# Mag_Ang.net
KiCad netlist of a schematic drawn in Altium Designer
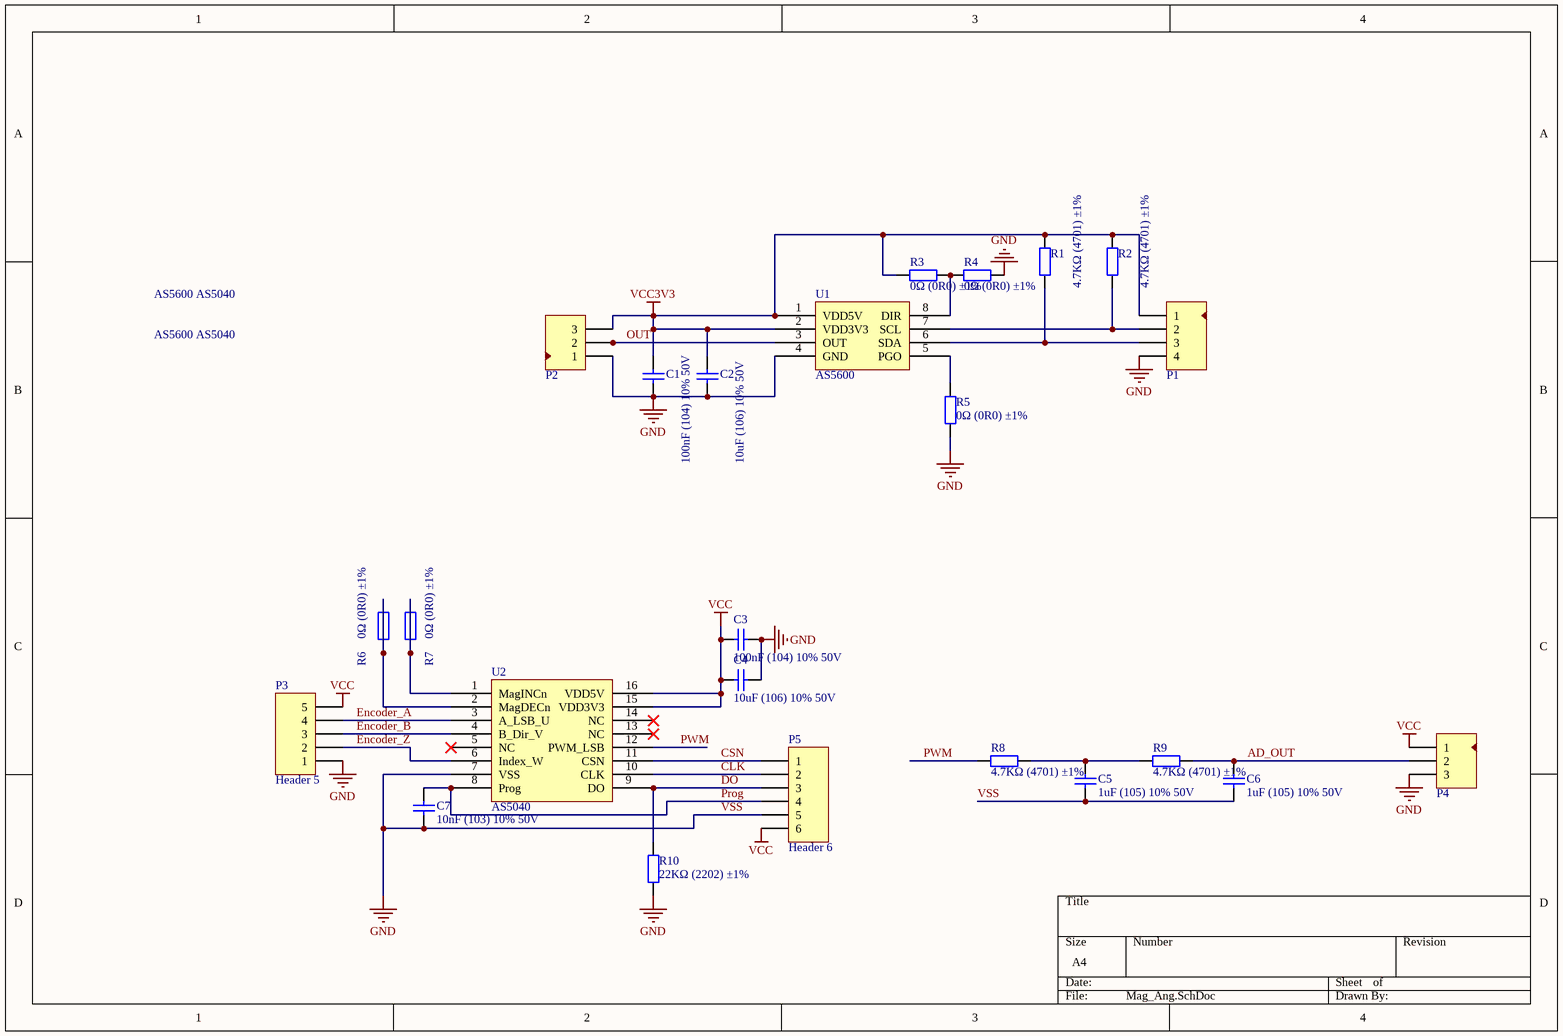
[diagram p0: Mag_Ang.SchDoc]

(export (version "E")
  (design (tool "Eeschema 10.0.6"))
  (components
    (comp (ref "C1")
      (value "100nF (104) 10% 50V")
      (footprint "0603_C")
      (description "贴片电容")
      (libsource (lib "Miscellaneous Devices LC") (part "0603 100nF (104) 10% 50V"))
    )
    (comp (ref "C2")
      (value "10uF (106) 10% 50V")
      (footprint "1206_C")
      (description "贴片电容")
      (libsource (lib "Miscellaneous Devices LC") (part "1206 10uF (106) 10% 50V"))
    )
    (comp (ref "C3")
      (value "100nF (104) 10% 50V")
      (footprint "0603_C")
      (description "贴片电容")
      (libsource (lib "Miscellaneous Devices LC") (part "0603 100nF (104) 10% 50V"))
    )
    (comp (ref "C4")
      (value "10uF (106) 10% 50V")
      (footprint "1206_C")
      (description "贴片电容")
      (libsource (lib "Miscellaneous Devices LC") (part "1206 10uF (106) 10% 50V"))
    )
    (comp (ref "C5")
      (value "1uF (105) 10% 50V")
      (footprint "0603_C")
      (description "贴片电容")
      (libsource (lib "Miscellaneous Devices LC") (part "0603 1uF (105) 10% 50V"))
    )
    (comp (ref "C6")
      (value "1uF (105) 10% 50V")
      (footprint "0603_C")
      (description "贴片电容")
      (libsource (lib "Miscellaneous Devices LC") (part "0603 1uF (105) 10% 50V"))
    )
    (comp (ref "C7")
      (value "10nF (103) 10% 50V")
      (footprint "0603_C")
      (description "贴片电容")
      (libsource (lib "Miscellaneous Devices LC") (part "0603 10nF (103) 10% 50V"))
    )
    (comp (ref "P1")
      (value "Header 4")
      (footprint "XH2.54-4P")
      (description "接插件")
      (fields (field (name "PUBLISHER") "Altium Limited"))
      (libsource (lib "HDR_fszhang") (part "Header 4"))
    )
    (comp (ref "P2")
      (value "Header 3")
      (footprint "KF2.54-3P")
      (description "接插件")
      (fields (field (name "PUBLISHER") "Altium Limited"))
      (libsource (lib "") (part "Header 3_1"))
    )
    (comp (ref "P3")
      (value "Header 5")
      (footprint "HDR1X5")
      (description "Header, 5-Pin")
      (fields (field (name "PUBLISHER") "Altium Limited"))
      (libsource (lib "Miscellaneous Connectors") (part "Header 5"))
    )
    (comp (ref "P4")
      (value "Header 3")
      (footprint "KF2.54-3P")
      (description "接插件")
      (fields (field (name "PUBLISHER") "Altium Limited"))
      (libsource (lib "HDR_fszhang") (part "Header 3"))
    )
    (comp (ref "P5")
      (value "Header 6")
      (footprint "HDR1X6")
      (description "Header, 6-Pin")
      (fields (field (name "PUBLISHER") "Altium Limited"))
      (libsource (lib "Miscellaneous Connectors") (part "Header 6"))
    )
    (comp (ref "R1")
      (value "4.7KΩ (4701) ±1%")
      (footprint "0603_R")
      (description "贴片电阻")
      (libsource (lib "") (part "0603 4.7KΩ (4701) 1%_1"))
    )
    (comp (ref "R2")
      (value "4.7KΩ (4701) ±1%")
      (footprint "0603_R")
      (description "贴片电阻")
      (libsource (lib "") (part "0603 4.7KΩ (4701) 1%_1"))
    )
    (comp (ref "R3")
      (value "0Ω (0R0) ±1%")
      (footprint "0603_R")
      (description "贴片电阻")
      (libsource (lib "") (part "0603 0Ω (0R0) 1%_1"))
    )
    (comp (ref "R4")
      (value "0Ω (0R0) ±1%")
      (footprint "0603_R")
      (description "贴片电阻")
      (libsource (lib "") (part "0603 0Ω (0R0) 1%_1"))
    )
    (comp (ref "R5")
      (value "0Ω (0R0) ±1%")
      (footprint "0603_R")
      (description "贴片电阻")
      (libsource (lib "") (part "0603 0Ω (0R0) 1%_2"))
    )
    (comp (ref "R6")
      (value "0Ω (0R0) ±1%")
      (footprint "0603_R")
      (description "贴片电阻")
      (libsource (lib "Miscellaneous Devices LC") (part "0603 0Ω (0R0) 1%"))
    )
    (comp (ref "R7")
      (value "0Ω (0R0) ±1%")
      (footprint "0603_R")
      (description "贴片电阻")
      (libsource (lib "Miscellaneous Devices LC") (part "0603 0Ω (0R0) 1%"))
    )
    (comp (ref "R8")
      (value "4.7KΩ (4701) ±1%")
      (footprint "0603_R")
      (description "贴片电阻")
      (libsource (lib "Miscellaneous Devices LC") (part "0603 4.7KΩ (4701) 1%"))
    )
    (comp (ref "R9")
      (value "4.7KΩ (4701) ±1%")
      (footprint "0603_R")
      (description "贴片电阻")
      (libsource (lib "Miscellaneous Devices LC") (part "0603 4.7KΩ (4701) 1%"))
    )
    (comp (ref "R10")
      (value "22KΩ (2202) ±1%")
      (footprint "0603_R")
      (description "贴片电阻")
      (libsource (lib "Miscellaneous Devices LC") (part "0603 22KΩ (2202) 1%"))
    )
    (comp (ref "U1") (value "AS5600") (footprint "RS2101S") (libsource (lib "Motorlib") (part "AS5600")))
    (comp (ref "U2")
      (value "AS5040")
      (footprint "SOP65P780X180-16N")
      (libsource (lib "Motorlib") (part "AS5040"))
    )
  )
  (nets
    (net (code "1") (name "/AD_OUT") (class "Default")
      (node (ref "C6") (pin "2") (pinfunction "2_2") (pintype "passive"))
      (node (ref "P4") (pin "2") (pinfunction "2_2") (pintype "passive"))
      (node (ref "R9") (pin "2") (pinfunction "2_2") (pintype "passive"))
    )
    (net (code "2") (name "/CLK") (class "Default")
      (node (ref "P5") (pin "2") (pinfunction "2_2") (pintype "passive"))
      (node (ref "U2") (pin "10") (pinfunction "CLK_10") (pintype "passive"))
    )
    (net (code "3") (name "/CSN") (class "Default")
      (node (ref "P5") (pin "1") (pinfunction "1_1") (pintype "passive"))
      (node (ref "U2") (pin "11") (pinfunction "CSN_11") (pintype "passive"))
    )
    (net (code "4") (name "/DO") (class "Default")
      (node (ref "P5") (pin "3") (pinfunction "3_3") (pintype "passive"))
      (node (ref "R10") (pin "2") (pinfunction "2_2") (pintype "passive"))
      (node (ref "U2") (pin "9") (pinfunction "DO_9") (pintype "passive"))
    )
    (net (code "5") (name "/Encoder_A") (class "Default")
      (node (ref "P3") (pin "4") (pinfunction "4_4") (pintype "passive"))
      (node (ref "U2") (pin "3") (pinfunction "A_LSB_U_3") (pintype "passive"))
    )
    (net (code "6") (name "/Encoder_B") (class "Default")
      (node (ref "P3") (pin "3") (pinfunction "3_3") (pintype "passive"))
      (node (ref "U2") (pin "4") (pinfunction "B_Dir_V_4") (pintype "passive"))
    )
    (net (code "7") (name "/Encoder_Z") (class "Default")
      (node (ref "P3") (pin "2") (pinfunction "2_2") (pintype "passive"))
      (node (ref "U2") (pin "6") (pinfunction "Index_W_6") (pintype "passive"))
    )
    (net (code "8") (name "/OUT") (class "Default")
      (node (ref "P2") (pin "2") (pinfunction "2_2") (pintype "passive"))
      (node (ref "U1") (pin "3") (pinfunction "OUT_3") (pintype "passive"))
    )
    (net (code "9") (name "/PWM") (class "Default")
      (node (ref "R8") (pin "1") (pinfunction "1_1") (pintype "passive"))
      (node (ref "U2") (pin "12") (pinfunction "PWM_LSB_12") (pintype "passive"))
    )
    (net (code "10") (name "/Prog") (class "Default")
      (node (ref "C7") (pin "2") (pinfunction "2_2") (pintype "passive"))
      (node (ref "P5") (pin "4") (pinfunction "4_4") (pintype "passive"))
      (node (ref "U2") (pin "8") (pinfunction "Prog_8") (pintype "passive"))
    )
    (net (code "11") (name "GND") (class "Default")
      (node (ref "C1") (pin "1") (pinfunction "1_1") (pintype "passive"))
      (node (ref "C2") (pin "1") (pinfunction "1_1") (pintype "passive"))
      (node (ref "C3") (pin "2") (pinfunction "2_2") (pintype "passive"))
      (node (ref "C4") (pin "1") (pinfunction "1_1") (pintype "passive"))
      (node (ref "C5") (pin "1") (pinfunction "1_1") (pintype "passive"))
      (node (ref "C6") (pin "1") (pinfunction "1_1") (pintype "passive"))
      (node (ref "C7") (pin "1") (pinfunction "1_1") (pintype "passive"))
      (node (ref "P1") (pin "4") (pinfunction "4_4") (pintype "passive"))
      (node (ref "P2") (pin "1") (pinfunction "1_1") (pintype "passive"))
      (node (ref "P3") (pin "1") (pinfunction "1_1") (pintype "passive"))
      (node (ref "P4") (pin "3") (pinfunction "3_3") (pintype "passive"))
      (node (ref "P5") (pin "5") (pinfunction "5_5") (pintype "passive"))
      (node (ref "R10") (pin "1") (pinfunction "1_1") (pintype "passive"))
      (node (ref "R4") (pin "1") (pinfunction "1_1") (pintype "passive"))
      (node (ref "R5") (pin "2") (pinfunction "2_2") (pintype "passive"))
      (node (ref "U1") (pin "4") (pinfunction "GND_4") (pintype "passive"))
      (node (ref "U2") (pin "7") (pinfunction "VSS_7") (pintype "passive"))
    )
    (net (code "12") (name "Net-(C5-Pad2)") (class "Default")
      (node (ref "C5") (pin "2") (pinfunction "2_2") (pintype "passive"))
      (node (ref "R8") (pin "2") (pinfunction "2_2") (pintype "passive"))
      (node (ref "R9") (pin "1") (pinfunction "1_1") (pintype "passive"))
    )
    (net (code "13") (name "Net-(U1-DIR)") (class "Default")
      (node (ref "R3") (pin "1") (pinfunction "1_1") (pintype "passive"))
      (node (ref "R4") (pin "2") (pinfunction "2_2") (pintype "passive"))
      (node (ref "U1") (pin "8") (pinfunction "DIR_8") (pintype "passive"))
    )
    (net (code "14") (name "Net-(U1-PGO)") (class "Default")
      (node (ref "R5") (pin "1") (pinfunction "1_1") (pintype "passive"))
      (node (ref "U1") (pin "5") (pinfunction "PGO_5") (pintype "passive"))
    )
    (net (code "15") (name "Net-(U1-SCL)") (class "Default")
      (node (ref "P1") (pin "2") (pinfunction "2_2") (pintype "passive"))
      (node (ref "R2") (pin "1") (pinfunction "1_1") (pintype "passive"))
      (node (ref "U1") (pin "7") (pinfunction "SCL_7") (pintype "passive"))
    )
    (net (code "16") (name "Net-(U1-SDA)") (class "Default")
      (node (ref "P1") (pin "3") (pinfunction "3_3") (pintype "passive"))
      (node (ref "R1") (pin "1") (pinfunction "1_1") (pintype "passive"))
      (node (ref "U1") (pin "6") (pinfunction "SDA_6") (pintype "passive"))
    )
    (net (code "17") (name "Net-(U2-MagDECn)") (class "Default")
      (node (ref "R6") (pin "1") (pinfunction "1_1") (pintype "passive"))
      (node (ref "R6") (pin "2") (pinfunction "2_2") (pintype "passive"))
      (node (ref "U2") (pin "2") (pinfunction "MagDECn_2") (pintype "passive"))
    )
    (net (code "18") (name "Net-(U2-MagINCn)") (class "Default")
      (node (ref "R7") (pin "1") (pinfunction "1_1") (pintype "passive"))
      (node (ref "R7") (pin "2") (pinfunction "2_2") (pintype "passive"))
      (node (ref "U2") (pin "1") (pinfunction "MagINCn_1") (pintype "passive"))
    )
    (net (code "19") (name "VCC") (class "Default")
      (node (ref "C3") (pin "1") (pinfunction "1_1") (pintype "passive"))
      (node (ref "C4") (pin "2") (pinfunction "2_2") (pintype "passive"))
      (node (ref "P3") (pin "5") (pinfunction "5_5") (pintype "passive"))
      (node (ref "P4") (pin "1") (pinfunction "1_1") (pintype "passive"))
      (node (ref "P5") (pin "6") (pinfunction "6_6") (pintype "passive"))
      (node (ref "U2") (pin "15") (pinfunction "VDD3V3_15") (pintype "passive"))
      (node (ref "U2") (pin "16") (pinfunction "VDD5V_16") (pintype "passive"))
    )
    (net (code "20") (name "VCC3V3") (class "Default")
      (node (ref "C1") (pin "2") (pinfunction "2_2") (pintype "passive"))
      (node (ref "C2") (pin "2") (pinfunction "2_2") (pintype "passive"))
      (node (ref "P1") (pin "1") (pinfunction "1_1") (pintype "passive"))
      (node (ref "P2") (pin "3") (pinfunction "3_3") (pintype "passive"))
      (node (ref "R1") (pin "2") (pinfunction "2_2") (pintype "passive"))
      (node (ref "R2") (pin "2") (pinfunction "2_2") (pintype "passive"))
      (node (ref "R3") (pin "2") (pinfunction "2_2") (pintype "passive"))
      (node (ref "U1") (pin "1") (pinfunction "VDD5V_1") (pintype "passive"))
      (node (ref "U1") (pin "2") (pinfunction "VDD3V3_2") (pintype "passive"))
    )
    (net (code "21") (name "unconnected-(U2-NC-Pad5)") (class "Default")
      (node (ref "U2") (pin "5") (pinfunction "NC_5") (pintype "passive+no_connect"))
    )
    (net (code "22") (name "unconnected-(U2-NC-Pad13)") (class "Default")
      (node (ref "U2") (pin "13") (pinfunction "NC_13") (pintype "passive+no_connect"))
    )
    (net (code "23") (name "unconnected-(U2-NC-Pad14)") (class "Default")
      (node (ref "U2") (pin "14") (pinfunction "NC_14") (pintype "passive+no_connect"))
    )
  )
)
